# badge1.net
KiCad netlist of a schematic drawn in EAGLE
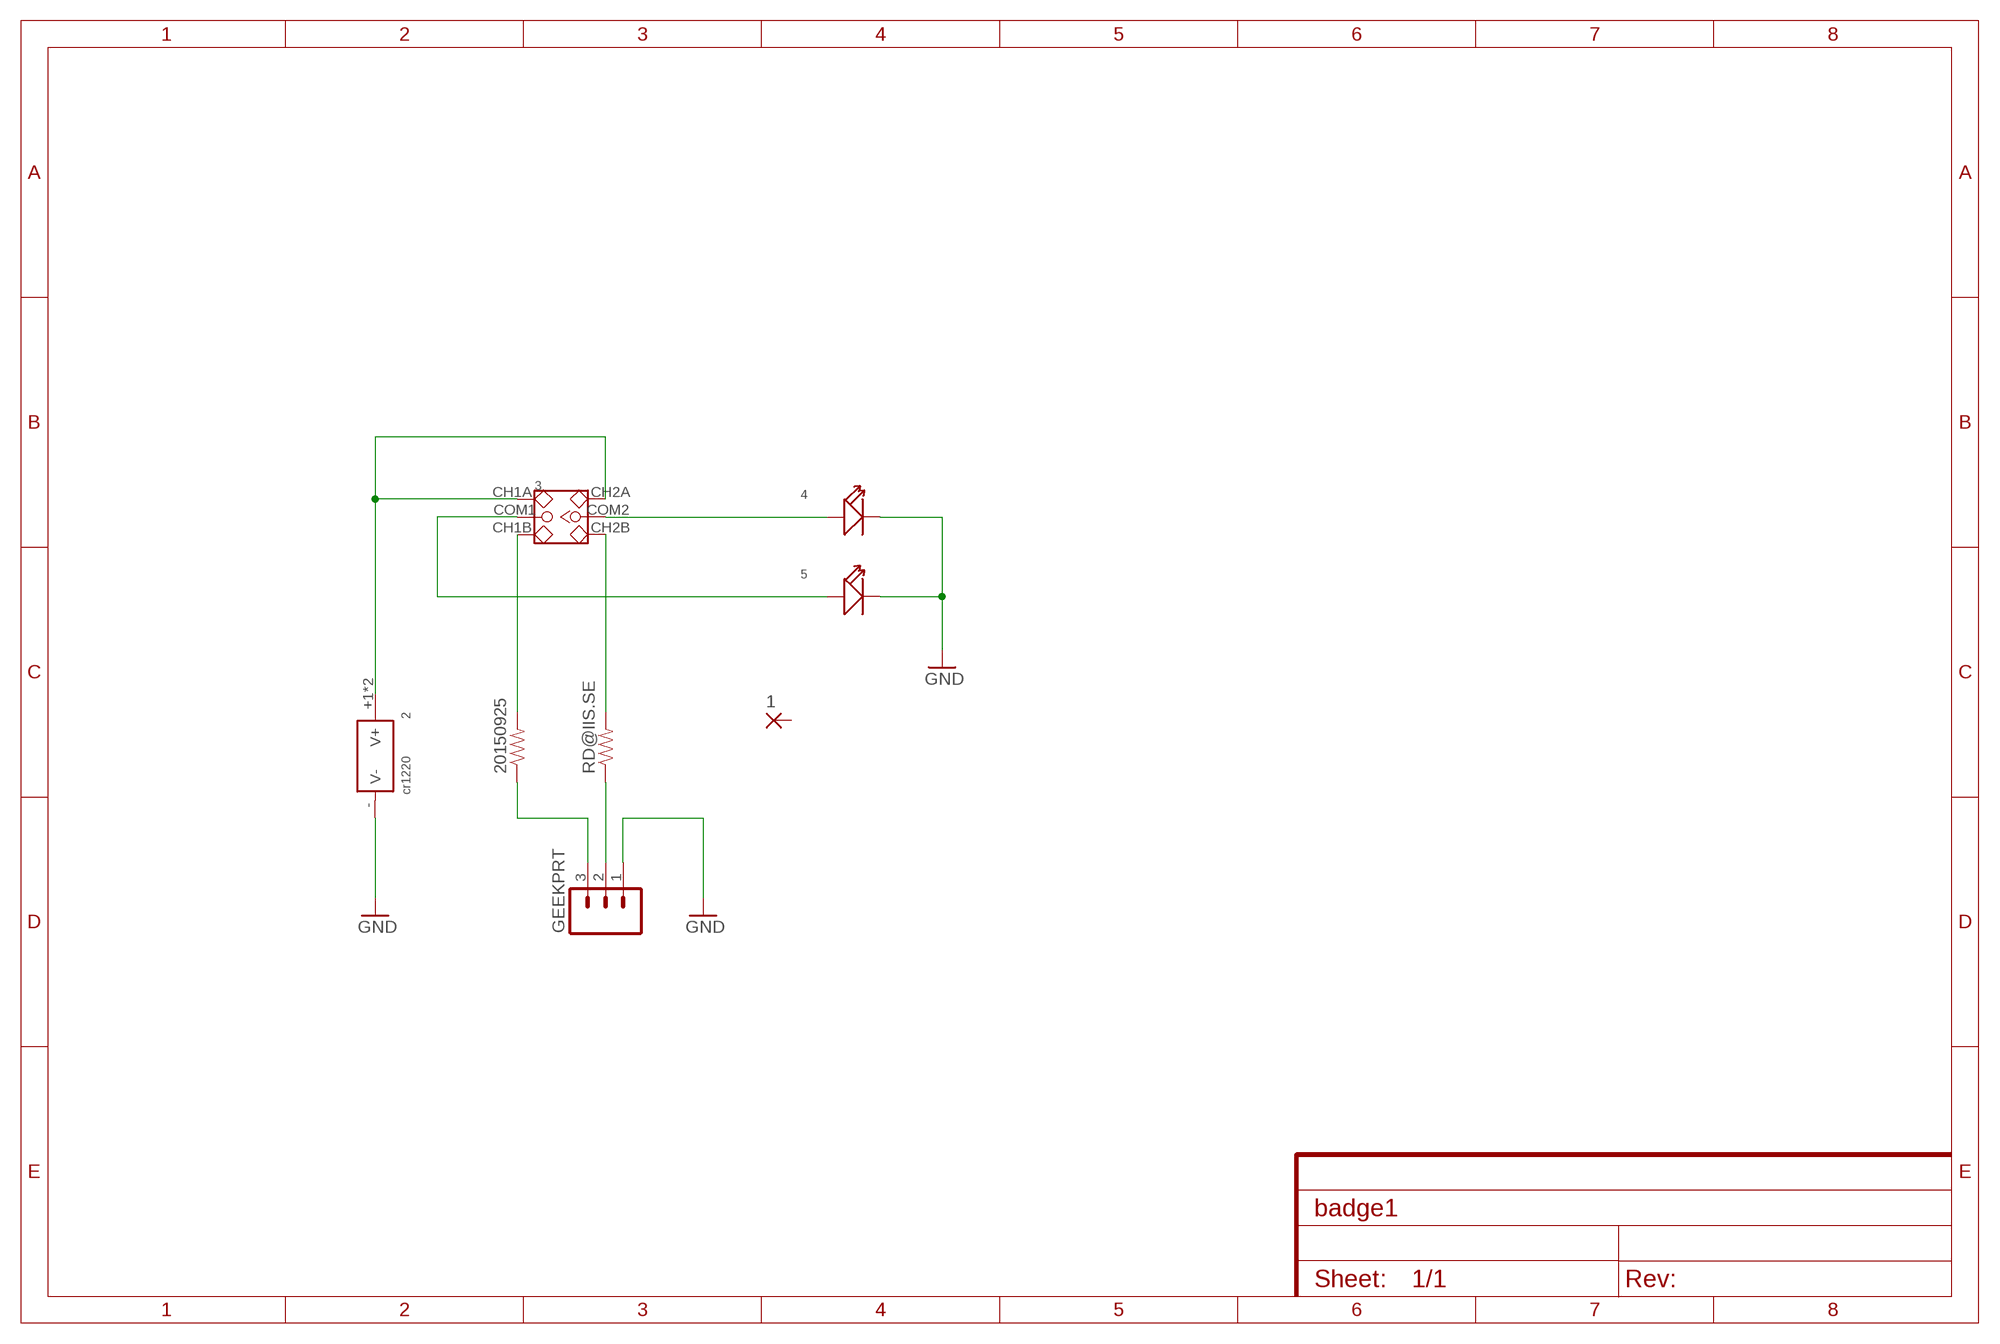
[diagram p0: schematic, sheet 1]

(export (version "E")
  (design (tool "Eeschema 10.0.6"))
  (components
    (comp (ref "1")
      (value "3,81/1,4")
      (footprint "eagle-import:3,81_1,4")
      (libsource (lib "eagle-import") (part "3,81/1,4"))
    )
    (comp (ref "2")
      (value "cr1220")
      (footprint "eagle-import:BAT2P-13.5-CR1220")
      (libsource (lib "eagle-import") (part "DIP-BATTERY-CELL-HOLDER(1220)"))
    )
    (comp (ref "3")
      (value "DIP-TOGGLE-SWITCH-2CH-(2X3P-2.54-90D)'90D'")
      (footprint "eagle-import:SW6-2.54-9.0X3.5X3.2MM-90D")
      (libsource (lib "eagle-import") (part "DIP-TOGGLE-SWITCH-2CH-(2X3P-2.54-90D)'90D'"))
    )
    (comp (ref "4")
      (value "LED'5MM'")
      (footprint "eagle-import:LED2-2.54-D5.0MM")
      (libsource (lib "eagle-import") (part "LED'5MM'"))
    )
    (comp (ref "5")
      (value "LED'5MM'")
      (footprint "eagle-import:LED2-2.54-D5.0MM")
      (libsource (lib "eagle-import") (part "LED'5MM'"))
    )
    (comp (ref "20150925")
      (value "RESISTORPTH-1/4W")
      (footprint "eagle-import:AXIAL-0.4")
      (libsource (lib "eagle-import") (part "RESISTORPTH-1/4W"))
    )
    (comp (ref "GEEKPRT")
      (value "M03LOCK")
      (footprint "eagle-import:1X03_LOCK")
      (libsource (lib "eagle-import") (part "M03LOCK"))
    )
    (comp (ref "RD@IIS.SE")
      (value "RESISTORPTH-1/4W")
      (footprint "eagle-import:AXIAL-0.4")
      (libsource (lib "eagle-import") (part "RESISTORPTH-1/4W"))
    )
  )
  (nets
    (net (code "1") (name "GND") (class "Default")
      (node (ref "2") (pin "-") (pinfunction "V-_-") (pintype "bidirectional"))
      (node (ref "4") (pin "-") (pinfunction "-_-") (pintype "passive"))
      (node (ref "5") (pin "-") (pinfunction "-_-") (pintype "passive"))
      (node (ref "GEEKPRT") (pin "1") (pinfunction "1_1") (pintype "passive"))
    )
    (net (code "2") (name "Net-(2-V+-Pad+1)") (class "Default")
      (node (ref "2") (pin "+1") (pinfunction "V+_+1") (pintype "bidirectional"))
      (node (ref "2") (pin "+2") (pinfunction "V+_+2") (pintype "bidirectional"))
      (node (ref "3") (pin "CH1A") (pinfunction "CH1A_CH1A") (pintype "bidirectional"))
      (node (ref "3") (pin "CH2A") (pinfunction "CH2A_CH2A") (pintype "bidirectional"))
    )
    (net (code "3") (name "Net-(3-PadCOM1)") (class "Default")
      (node (ref "3") (pin "COM1") (pinfunction "COM1_COM1") (pintype "bidirectional"))
      (node (ref "5") (pin "+") (pinfunction "+_+") (pintype "passive"))
    )
    (net (code "4") (name "Net-(3-PadCOM2)") (class "Default")
      (node (ref "3") (pin "COM2") (pinfunction "COM2_COM2") (pintype "bidirectional"))
      (node (ref "4") (pin "+") (pinfunction "+_+") (pintype "passive"))
    )
    (net (code "5") (name "Net-(20150925-1)") (class "Default")
      (node (ref "20150925") (pin "P$1") (pinfunction "1_P$1") (pintype "passive"))
      (node (ref "GEEKPRT") (pin "3") (pinfunction "3_3") (pintype "passive"))
    )
    (net (code "6") (name "Net-(20150925-2)") (class "Default")
      (node (ref "20150925") (pin "P$2") (pinfunction "2_P$2") (pintype "passive"))
      (node (ref "3") (pin "CH1B") (pinfunction "CH1B_CH1B") (pintype "bidirectional"))
    )
    (net (code "7") (name "Net-(RD@IIS.SE-1)") (class "Default")
      (node (ref "GEEKPRT") (pin "2") (pinfunction "2_2") (pintype "passive"))
      (node (ref "RD@IIS.SE") (pin "P$1") (pinfunction "1_P$1") (pintype "passive"))
    )
    (net (code "8") (name "Net-(RD@IIS.SE-2)") (class "Default")
      (node (ref "3") (pin "CH2B") (pinfunction "CH2B_CH2B") (pintype "bidirectional"))
      (node (ref "RD@IIS.SE") (pin "P$2") (pinfunction "2_P$2") (pintype "passive"))
    )
    (net (code "9") (name "unconnected-(1-P-Pad1)") (class "Default")
      (node (ref "1") (pin "1") (pinfunction "P_1") (pintype "passive"))
    )
  )
)
